# Schematic-Altium.net
KiCad netlist of a schematic drawn in Altium Designer
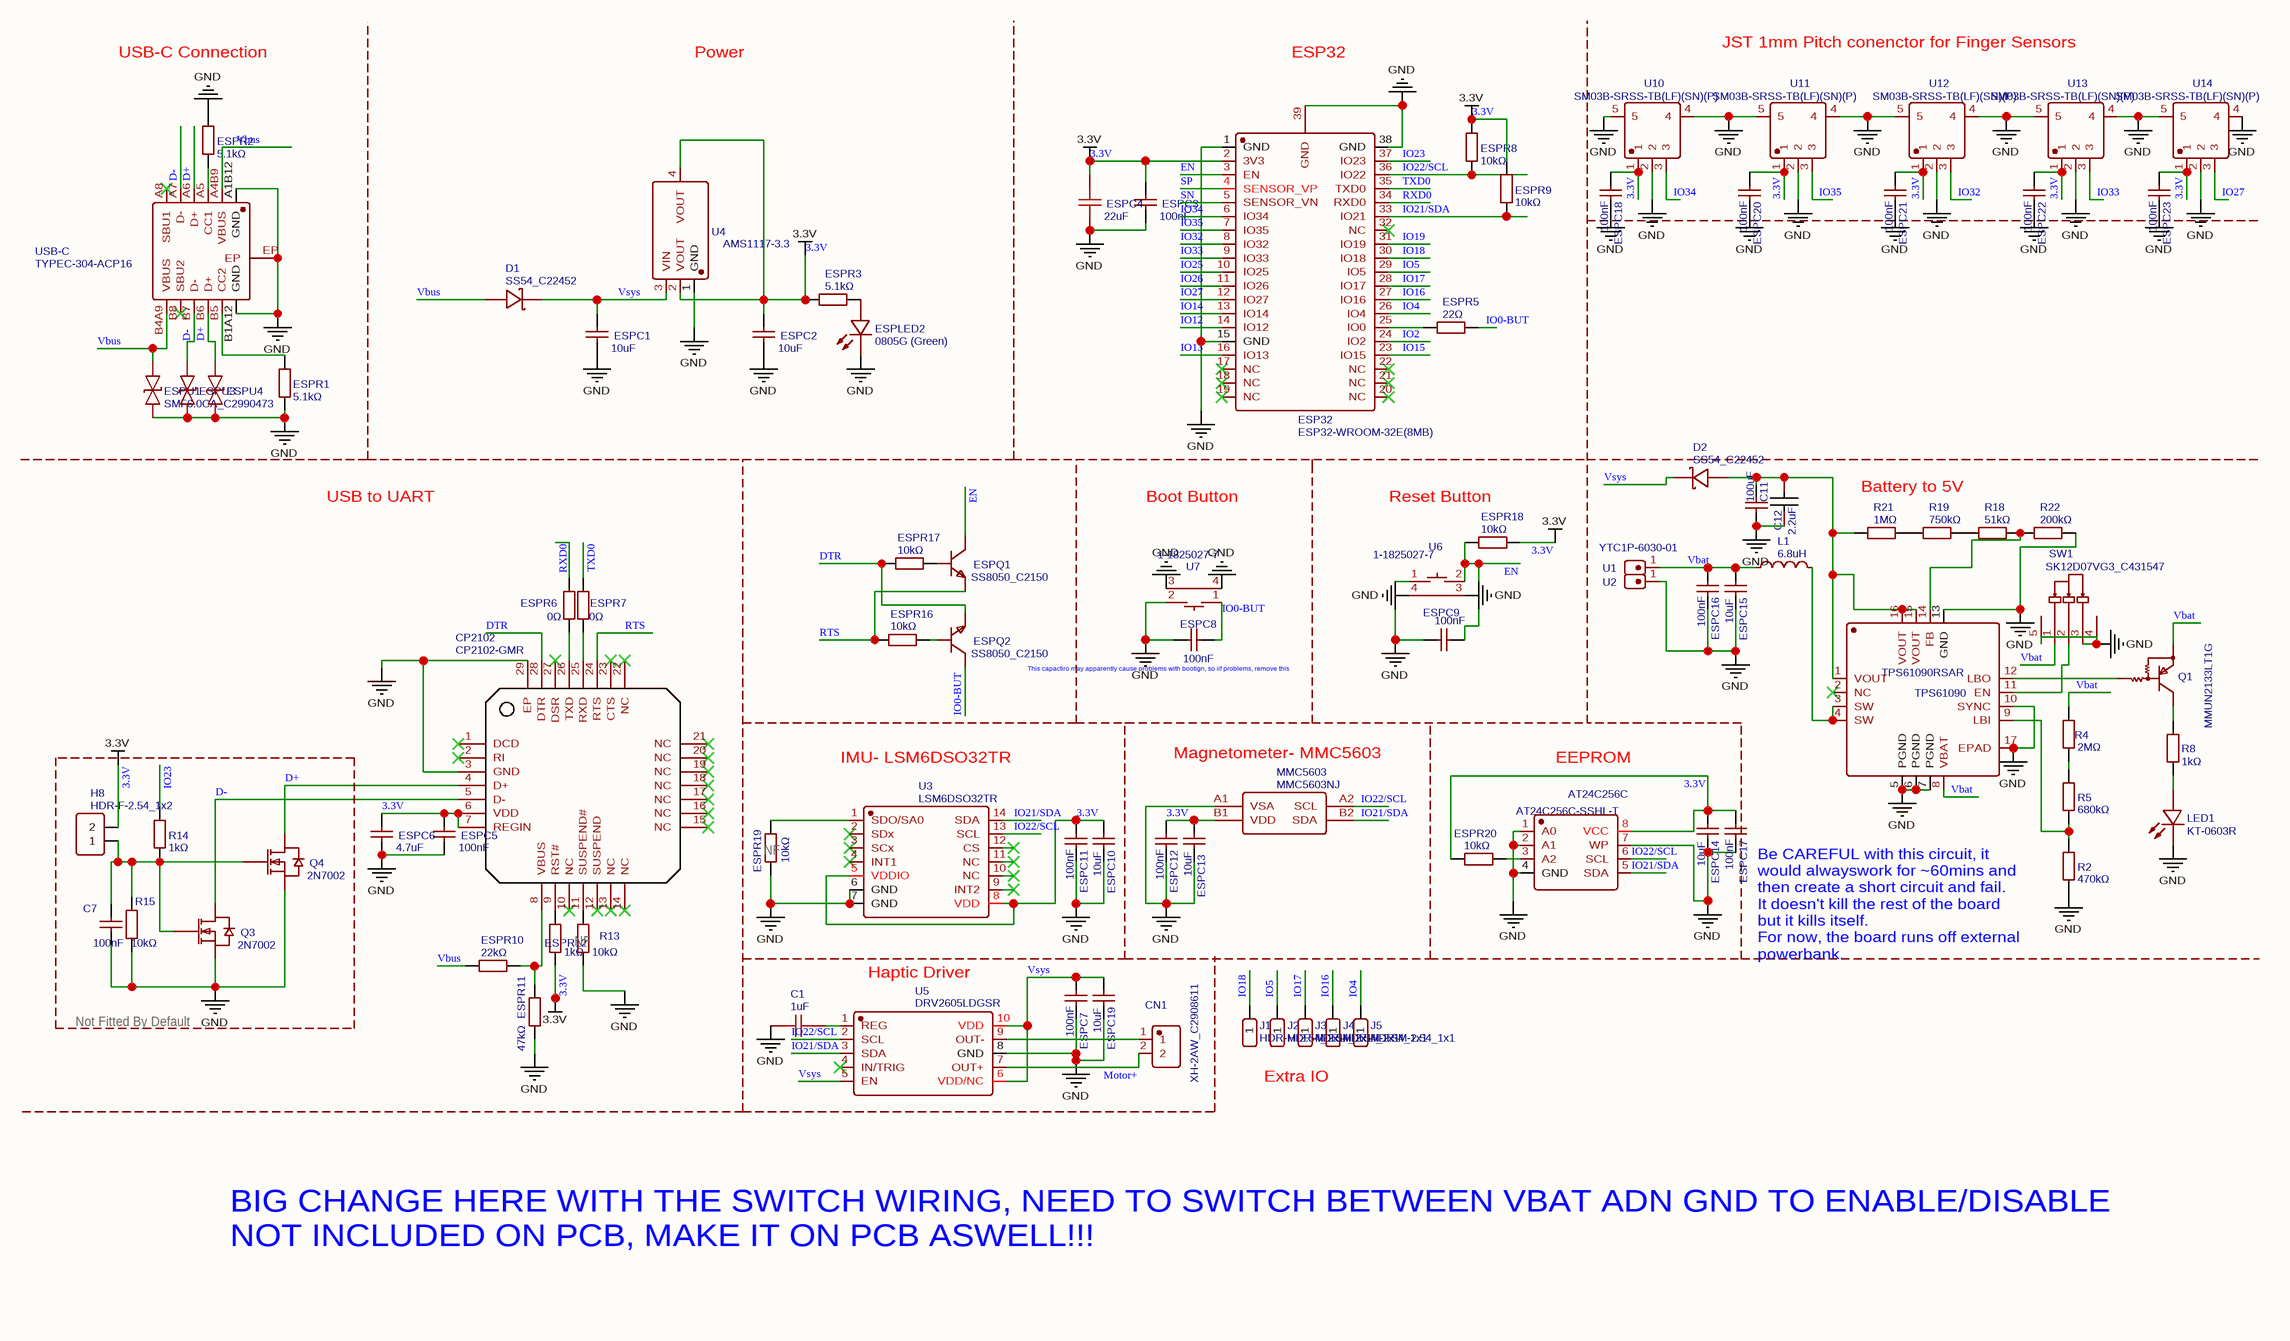
[diagram p0: Schematic-Altium.schdoc]

(export (version "E")
  (design (tool "Eeschema 10.0.6"))
  (components
    (comp (ref "AT24C256C")
      (value "AT24C256C-SSHL-T")
      (fields (field (name "MANUFACTURER") "MICROCHIP(美国微芯)"))
      (libsource (lib "altium-import") (part "root_0_AT24C256C-SSHL-T_"))
    )
    (comp (ref "C1")
      (value "1uF")
      (fields
        (field (name "MANUFACTURER") "SAMSUNG(三星)")
        (field (name "MANUFACTURER PART") "CL05A105KA5NQNC")
      )
      (libsource (lib "altium-import") (part "root_0_1uF_"))
    )
    (comp (ref "C7")
      (value "100nF")
      (fields
        (field (name "MANUFACTURER PART") "CL05B104KO5NNNC")
        (field (name "MANUFACTURER") "SAMSUNG(三星)")
      )
      (libsource (lib "altium-import") (part "root_1_100nF_"))
    )
    (comp (ref "C11")
      (value "100uF")
      (fields
        (field (name "MANUFACTURER PART") "CL31A107MQHNNNE")
        (field (name "MANUFACTURER") "SAMSUNG(三星)")
      )
      (libsource (lib "altium-import") (part "root_1_100uF_"))
    )
    (comp (ref "C12")
      (value "2.2uF")
      (fields
        (field (name "MANUFACTURER PART") "CL05A225MQ5NSNC")
        (field (name "MANUFACTURER") "SAMSUNG(三星)")
      )
      (libsource (lib "altium-import") (part "root_1_2.2uF_"))
    )
    (comp (ref "CN1")
      (value "XH-2AW_C2908611")
      (fields
        (field (name "MANUFACTURER") "HCTL(华灿天禄)")
        (field (name "MANUFACTURER PART") "XH-2AW")
        (field (name "CONTRIBUTOR") "LCSC")
      )
      (libsource (lib "altium-import") (part "root_0_XH-2AW_C2908611_"))
    )
    (comp (ref "CP2102")
      (value "CP2102-GMR")
      (fields (field (name "MANUFACTURER") "SILICON LABS(芯科)"))
      (libsource (lib "altium-import") (part "root_0_CP2102-GMR_"))
    )
    (comp (ref "D1")
      (value "SS54_C22452")
      (fields (field (name "MANUFACTURER PART") "SS54") (field (name "MANUFACTURER") "MDD"))
      (libsource (lib "altium-import") (part "root_2_SS54_C22452_"))
    )
    (comp (ref "D2")
      (value "SS54_C22452")
      (fields (field (name "MANUFACTURER PART") "SS54") (field (name "MANUFACTURER") "MDD"))
      (libsource (lib "altium-import") (part "root_0_SS54_C22452_"))
    )
    (comp (ref "ESP32")
      (value "ESP32-WROOM-32E(8MB)")
      (fields
        (field (name "MANUFACTURER") "ESPRESSIF(乐鑫)")
        (field (name "MANUFACTURER PART") "ESP32-WROOM-32E-N8")
        (field (name "CONTRIBUTOR") "LCSC")
      )
      (libsource (lib "altium-import") (part "root_0_ESP32-WROOM-32E(8MB)_"))
    )
    (comp (ref "ESPC1")
      (value "10uF")
      (fields
        (field (name "MANUFACTURER PART") "CL05A106MQ5NUNC")
        (field (name "MANUFACTURER") "SAMSUNG(三星)")
      )
      (libsource (lib "altium-import") (part "root_1_10uF_"))
    )
    (comp (ref "ESPC2")
      (value "10uF")
      (fields
        (field (name "MANUFACTURER PART") "CL05A106MQ5NUNC")
        (field (name "MANUFACTURER") "SAMSUNG(三星)")
      )
      (libsource (lib "altium-import") (part "root_1_10uF_"))
    )
    (comp (ref "ESPC3")
      (value "100nF")
      (fields
        (field (name "MANUFACTURER PART") "CL05B104KO5NNNC")
        (field (name "MANUFACTURER") "SAMSUNG(三星)")
      )
      (libsource (lib "altium-import") (part "root_1_100nF_"))
    )
    (comp (ref "ESPC4")
      (value "22uF")
      (fields
        (field (name "MANUFACTURER") "SAMSUNG(三星)")
        (field (name "MANUFACTURER PART") "CL10A226MQ8NRNC")
      )
      (libsource (lib "altium-import") (part "root_1_22uF_"))
    )
    (comp (ref "ESPC5")
      (value "100nF")
      (fields
        (field (name "MANUFACTURER PART") "CL05B104KO5NNNC")
        (field (name "MANUFACTURER") "SAMSUNG(三星)")
      )
      (libsource (lib "altium-import") (part "root_1_100nF_"))
    )
    (comp (ref "ESPC6")
      (value "4.7uF")
      (fields
        (field (name "MANUFACTURER PART") "CL05A475MP5NRNC")
        (field (name "MANUFACTURER") "SAMSUNG(三星)")
      )
      (libsource (lib "altium-import") (part "root_1_4.7uF_"))
    )
    (comp (ref "ESPC7")
      (value "100nF")
      (fields
        (field (name "MANUFACTURER PART") "CL05B104KO5NNNC")
        (field (name "MANUFACTURER") "SAMSUNG(三星)")
      )
      (libsource (lib "altium-import") (part "root_3_100nF_"))
    )
    (comp (ref "ESPC8")
      (value "100nF")
      (fields
        (field (name "MANUFACTURER PART") "CL05B104KO5NNNC")
        (field (name "MANUFACTURER") "SAMSUNG(三星)")
      )
      (libsource (lib "altium-import") (part "root_0_100nF_"))
    )
    (comp (ref "ESPC9")
      (value "100nF")
      (fields
        (field (name "MANUFACTURER PART") "CL05B104KO5NNNC")
        (field (name "MANUFACTURER") "SAMSUNG(三星)")
      )
      (libsource (lib "altium-import") (part "root_0_100nF_"))
    )
    (comp (ref "ESPC10")
      (value "10uF")
      (fields
        (field (name "MANUFACTURER PART") "CL05A106MQ5NUNC")
        (field (name "MANUFACTURER") "SAMSUNG(三星)")
      )
      (libsource (lib "altium-import") (part "root_1_10uF_"))
    )
    (comp (ref "ESPC11")
      (value "100nF")
      (fields
        (field (name "MANUFACTURER PART") "CL05B104KO5NNNC")
        (field (name "MANUFACTURER") "SAMSUNG(三星)")
      )
      (libsource (lib "altium-import") (part "root_3_100nF_"))
    )
    (comp (ref "ESPC12")
      (value "100nF")
      (fields
        (field (name "MANUFACTURER PART") "CL05B104KO5NNNC")
        (field (name "MANUFACTURER") "SAMSUNG(三星)")
      )
      (libsource (lib "altium-import") (part "root_3_100nF_"))
    )
    (comp (ref "ESPC13")
      (value "10uF")
      (fields
        (field (name "MANUFACTURER PART") "CL05A106MQ5NUNC")
        (field (name "MANUFACTURER") "SAMSUNG(三星)")
      )
      (libsource (lib "altium-import") (part "root_1_10uF_"))
    )
    (comp (ref "ESPC14")
      (value "10uF")
      (fields
        (field (name "MANUFACTURER PART") "CL05A106MQ5NUNC")
        (field (name "MANUFACTURER") "SAMSUNG(三星)")
      )
      (libsource (lib "altium-import") (part "root_1_10uF_"))
    )
    (comp (ref "ESPC15")
      (value "10uF")
      (fields
        (field (name "MANUFACTURER PART") "CL05A106MQ5NUNC")
        (field (name "MANUFACTURER") "SAMSUNG(三星)")
      )
      (libsource (lib "altium-import") (part "root_1_10uF_"))
    )
    (comp (ref "ESPC16")
      (value "100nF")
      (fields
        (field (name "MANUFACTURER PART") "CL05B104KO5NNNC")
        (field (name "MANUFACTURER") "SAMSUNG(三星)")
      )
      (libsource (lib "altium-import") (part "root_3_100nF_"))
    )
    (comp (ref "ESPC17")
      (value "100nF")
      (fields
        (field (name "MANUFACTURER PART") "CL05B104KO5NNNC")
        (field (name "MANUFACTURER") "SAMSUNG(三星)")
      )
      (libsource (lib "altium-import") (part "root_3_100nF_"))
    )
    (comp (ref "ESPC18")
      (value "100nF")
      (fields
        (field (name "MANUFACTURER PART") "CL05B104KO5NNNC")
        (field (name "MANUFACTURER") "SAMSUNG(三星)")
      )
      (libsource (lib "altium-import") (part "root_3_100nF_"))
    )
    (comp (ref "ESPC19")
      (value "10uF")
      (fields
        (field (name "MANUFACTURER PART") "CL05A106MQ5NUNC")
        (field (name "MANUFACTURER") "SAMSUNG(三星)")
      )
      (libsource (lib "altium-import") (part "root_1_10uF_"))
    )
    (comp (ref "ESPC20")
      (value "100nF")
      (fields
        (field (name "MANUFACTURER PART") "CL05B104KO5NNNC")
        (field (name "MANUFACTURER") "SAMSUNG(三星)")
      )
      (libsource (lib "altium-import") (part "root_3_100nF_"))
    )
    (comp (ref "ESPC21")
      (value "100nF")
      (fields
        (field (name "MANUFACTURER PART") "CL05B104KO5NNNC")
        (field (name "MANUFACTURER") "SAMSUNG(三星)")
      )
      (libsource (lib "altium-import") (part "root_3_100nF_"))
    )
    (comp (ref "ESPC22")
      (value "100nF")
      (fields
        (field (name "MANUFACTURER PART") "CL05B104KO5NNNC")
        (field (name "MANUFACTURER") "SAMSUNG(三星)")
      )
      (libsource (lib "altium-import") (part "root_3_100nF_"))
    )
    (comp (ref "ESPC23")
      (value "100nF")
      (fields
        (field (name "MANUFACTURER PART") "CL05B104KO5NNNC")
        (field (name "MANUFACTURER") "SAMSUNG(三星)")
      )
      (libsource (lib "altium-import") (part "root_3_100nF_"))
    )
    (comp (ref "ESPLED2")
      (value "0805G (Green)")
      (fields (field (name "MANUFACTURER") "KENTO") (field (name "MANUFACTURER PART") "KT-0805翠绿"))
      (libsource (lib "altium-import") (part "root_1_0805G (Green)_"))
    )
    (comp (ref "ESPQ1")
      (value "SS8050_C2150")
      (fields (field (name "MANUFACTURER") "CJ(江苏长电/长晶)") (field (name "MANUFACTURER PART") "SS8050"))
      (libsource (lib "altium-import") (part "root_0_SS8050_C2150_"))
    )
    (comp (ref "ESPQ2")
      (value "SS8050_C2150")
      (fields (field (name "MANUFACTURER") "CJ(江苏长电/长晶)") (field (name "MANUFACTURER PART") "SS8050"))
      (libsource (lib "") (part "root_0_SS8050_C2150__1"))
    )
    (comp (ref "ESPR1")
      (value "5.1kΩ")
      (fields
        (field (name "MANUFACTURER") "UNI-ROYAL(厚声)")
        (field (name "MANUFACTURER PART") "0402WGF5101TCE")
      )
      (libsource (lib "altium-import") (part "root_1_5.1kΩ_"))
    )
    (comp (ref "ESPR2")
      (value "5.1kΩ")
      (fields
        (field (name "MANUFACTURER") "UNI-ROYAL(厚声)")
        (field (name "MANUFACTURER PART") "0402WGF5101TCE")
      )
      (libsource (lib "altium-import") (part "root_1_5.1kΩ_"))
    )
    (comp (ref "ESPR3")
      (value "5.1kΩ")
      (fields
        (field (name "MANUFACTURER") "UNI-ROYAL(厚声)")
        (field (name "MANUFACTURER PART") "0402WGF5101TCE")
      )
      (libsource (lib "altium-import") (part "root_2_5.1kΩ_"))
    )
    (comp (ref "ESPR5")
      (value "22Ω")
      (fields
        (field (name "MANUFACTURER") "UNI-ROYAL(厚声)")
        (field (name "MANUFACTURER PART") "0402WGF220JTCE")
      )
      (libsource (lib "altium-import") (part "root_0_22Ω_"))
    )
    (comp (ref "ESPR6")
      (value "0Ω")
      (fields
        (field (name "MANUFACTURER") "UNI-ROYAL(厚声)")
        (field (name "MANUFACTURER PART") "0402WGF0000TCE")
      )
      (libsource (lib "altium-import") (part "root_1_0Ω_"))
    )
    (comp (ref "ESPR7")
      (value "0Ω")
      (fields
        (field (name "MANUFACTURER") "UNI-ROYAL(厚声)")
        (field (name "MANUFACTURER PART") "0402WGF0000TCE")
      )
      (libsource (lib "altium-import") (part "root_1_0Ω_"))
    )
    (comp (ref "ESPR8")
      (value "10kΩ")
      (fields
        (field (name "MANUFACTURER") "UNI-ROYAL(厚声)")
        (field (name "MANUFACTURER PART") "0402WGF1002TCE")
      )
      (libsource (lib "altium-import") (part "root_1_10kΩ_"))
    )
    (comp (ref "ESPR9")
      (value "10kΩ")
      (fields
        (field (name "MANUFACTURER") "UNI-ROYAL(厚声)")
        (field (name "MANUFACTURER PART") "0402WGF1002TCE")
      )
      (libsource (lib "altium-import") (part "root_1_10kΩ_"))
    )
    (comp (ref "ESPR10")
      (value "22kΩ")
      (fields
        (field (name "MANUFACTURER") "UNI-ROYAL(厚声)")
        (field (name "MANUFACTURER PART") "0402WGF2202TCE")
      )
      (libsource (lib "altium-import") (part "root_0_22kΩ_"))
    )
    (comp (ref "ESPR11")
      (value "47kΩ")
      (fields
        (field (name "MANUFACTURER") "UNI-ROYAL(厚声)")
        (field (name "MANUFACTURER PART") "0402WGF4702TCE")
      )
      (libsource (lib "altium-import") (part "root_1_47kΩ_"))
    )
    (comp (ref "ESPR12")
      (value "1kΩ")
      (fields
        (field (name "MANUFACTURER") "UNI-ROYAL(厚声)")
        (field (name "MANUFACTURER PART") "0402WGF1001TCE")
      )
      (libsource (lib "altium-import") (part "root_1_1kΩ_"))
    )
    (comp (ref "ESPR16")
      (value "10kΩ")
      (fields
        (field (name "MANUFACTURER") "UNI-ROYAL(厚声)")
        (field (name "MANUFACTURER PART") "0402WGF1002TCE")
      )
      (libsource (lib "altium-import") (part "root_2_10kΩ_"))
    )
    (comp (ref "ESPR17")
      (value "10kΩ")
      (fields
        (field (name "MANUFACTURER") "UNI-ROYAL(厚声)")
        (field (name "MANUFACTURER PART") "0402WGF1002TCE")
      )
      (libsource (lib "altium-import") (part "root_2_10kΩ_"))
    )
    (comp (ref "ESPR18")
      (value "10kΩ")
      (fields
        (field (name "MANUFACTURER") "UNI-ROYAL(厚声)")
        (field (name "MANUFACTURER PART") "0402WGF1002TCE")
      )
      (libsource (lib "altium-import") (part "root_2_10kΩ_"))
    )
    (comp (ref "ESPR19")
      (value "10kΩ")
      (fields
        (field (name "MANUFACTURER") "UNI-ROYAL(厚声)")
        (field (name "MANUFACTURER PART") "0402WGF1002TCE")
      )
      (libsource (lib "altium-import") (part "root_1_10kΩ_"))
    )
    (comp (ref "ESPR20")
      (value "10kΩ")
      (fields
        (field (name "MANUFACTURER") "UNI-ROYAL(厚声)")
        (field (name "MANUFACTURER PART") "0402WGF1002TCE")
      )
      (libsource (lib "altium-import") (part "root_2_10kΩ_"))
    )
    (comp (ref "ESPU1")
      (value "SMF6.0CA_C2990473")
      (fields
        (field (name "MANUFACTURER") "Liown(里阳半导体)")
        (field (name "MANUFACTURER PART") "SMF6.0CA")
        (field (name "CONTRIBUTOR") "lcsc")
      )
      (libsource (lib "altium-import") (part "root_1_SMF6.0CA_C2990473_"))
    )
    (comp (ref "ESPU3")
      (value "SMF6.0CA_C2990473")
      (fields
        (field (name "MANUFACTURER") "Liown(里阳半导体)")
        (field (name "MANUFACTURER PART") "SMF6.0CA")
        (field (name "CONTRIBUTOR") "lcsc")
      )
      (libsource (lib "altium-import") (part "root_1_SMF6.0CA_C2990473_"))
    )
    (comp (ref "ESPU4")
      (value "SMF6.0CA_C2990473")
      (fields
        (field (name "MANUFACTURER") "Liown(里阳半导体)")
        (field (name "MANUFACTURER PART") "SMF6.0CA")
        (field (name "CONTRIBUTOR") "lcsc")
      )
      (libsource (lib "altium-import") (part "root_1_SMF6.0CA_C2990473_"))
    )
    (comp (ref "H8")
      (value "HDR-F-2.54_1x2")
      (fields (field (name "CONTRIBUTOR") "LCEDA_Lib"))
      (libsource (lib "altium-import") (part "root_2_HDR-F-2.54_1x2_"))
    )
    (comp (ref "J1")
      (value "HDR-M-2.54_1x1")
      (fields (field (name "CONTRIBUTOR") "LCEDA_Lib"))
      (libsource (lib "altium-import") (part "root_3_HDR-M-2.54_1x1_"))
    )
    (comp (ref "J2")
      (value "HDR-M-2.54_1x1")
      (fields (field (name "CONTRIBUTOR") "LCEDA_Lib"))
      (libsource (lib "altium-import") (part "root_3_HDR-M-2.54_1x1_"))
    )
    (comp (ref "J3")
      (value "HDR-M-2.54_1x1")
      (fields (field (name "CONTRIBUTOR") "LCEDA_Lib"))
      (libsource (lib "altium-import") (part "root_3_HDR-M-2.54_1x1_"))
    )
    (comp (ref "J4")
      (value "HDR-M-2.54_1x1")
      (fields (field (name "CONTRIBUTOR") "LCEDA_Lib"))
      (libsource (lib "altium-import") (part "root_3_HDR-M-2.54_1x1_"))
    )
    (comp (ref "J5")
      (value "HDR-M-2.54_1x1")
      (fields (field (name "CONTRIBUTOR") "LCEDA_Lib"))
      (libsource (lib "altium-import") (part "root_3_HDR-M-2.54_1x1_"))
    )
    (comp (ref "L1")
      (value "6.8uH")
      (fields
        (field (name "MANUFACTURER") "SXN(顺翔诺)")
        (field (name "MANUFACTURER PART") "SMMS0420-6R8M")
        (field (name "CONTRIBUTOR") "LCSC")
      )
      (libsource (lib "altium-import") (part "root_0_6.8uH_"))
    )
    (comp (ref "LED1")
      (value "KT-0603R")
      (fields (field (name "MANUFACTURER") "KENTO"))
      (libsource (lib "altium-import") (part "root_1_KT-0603R_"))
    )
    (comp (ref "MMC5603")
      (value "MMC5603NJ")
      (fields (field (name "MANUFACTURER") "MEMSIC(美新)") (field (name "CONTRIBUTOR") "LCSC"))
      (libsource (lib "altium-import") (part "root_0_MMC5603NJ_"))
    )
    (comp (ref "Q1")
      (value "MMUN2133LT1G")
      (fields (field (name "MANUFACTURER") "onsemi(安森美)"))
      (libsource (lib "altium-import") (part "root_0_MMUN2133LT1G_"))
    )
    (comp (ref "Q3")
      (value "2N7002")
      (fields (field (name "MANUFACTURER") "CJ(江苏长电/长晶)"))
      (libsource (lib "altium-import") (part "root_0_2N7002_"))
    )
    (comp (ref "Q4")
      (value "2N7002")
      (fields (field (name "MANUFACTURER") "CJ(江苏长电/长晶)"))
      (libsource (lib "altium-import") (part "root_0_2N7002_"))
    )
    (comp (ref "R2")
      (value "470kΩ")
      (fields
        (field (name "MANUFACTURER") "UNI-ROYAL(厚声)")
        (field (name "MANUFACTURER PART") "0402WGF4703TCE")
      )
      (libsource (lib "altium-import") (part "root_1_470kΩ_"))
    )
    (comp (ref "R4")
      (value "2MΩ")
      (fields
        (field (name "MANUFACTURER") "UNI-ROYAL(厚声)")
        (field (name "MANUFACTURER PART") "0603WAF2004T5E")
      )
      (libsource (lib "altium-import") (part "root_1_2MΩ_"))
    )
    (comp (ref "R5")
      (value "680kΩ")
      (fields
        (field (name "MANUFACTURER") "UNI-ROYAL(厚声)")
        (field (name "MANUFACTURER PART") "0603WAF6803T5E")
      )
      (libsource (lib "altium-import") (part "root_1_680kΩ_"))
    )
    (comp (ref "R8")
      (value "1kΩ")
      (fields
        (field (name "MANUFACTURER") "UNI-ROYAL(厚声)")
        (field (name "MANUFACTURER PART") "0402WGF1001TCE")
      )
      (libsource (lib "altium-import") (part "root_1_1kΩ_"))
    )
    (comp (ref "R13")
      (value "10kΩ")
      (fields
        (field (name "MANUFACTURER") "UNI-ROYAL(厚声)")
        (field (name "MANUFACTURER PART") "0402WGF1002TCE")
      )
      (libsource (lib "altium-import") (part "root_1_10kΩ_"))
    )
    (comp (ref "R14")
      (value "1kΩ")
      (fields
        (field (name "MANUFACTURER") "UNI-ROYAL(厚声)")
        (field (name "MANUFACTURER PART") "0402WGF1001TCE")
      )
      (libsource (lib "altium-import") (part "root_1_1kΩ_"))
    )
    (comp (ref "R15")
      (value "10kΩ")
      (fields
        (field (name "MANUFACTURER") "UNI-ROYAL(厚声)")
        (field (name "MANUFACTURER PART") "0402WGF1002TCE")
      )
      (libsource (lib "altium-import") (part "root_1_10kΩ_"))
    )
    (comp (ref "R18")
      (value "51kΩ")
      (fields
        (field (name "MANUFACTURER") "UNI-ROYAL(厚声)")
        (field (name "MANUFACTURER PART") "0402WGF5102TCE")
      )
      (libsource (lib "altium-import") (part "root_0_51kΩ_"))
    )
    (comp (ref "R19")
      (value "750kΩ")
      (fields
        (field (name "MANUFACTURER") "UNI-ROYAL(厚声)")
        (field (name "MANUFACTURER PART") "0603WAF7503T5E")
      )
      (libsource (lib "altium-import") (part "root_0_750kΩ_"))
    )
    (comp (ref "R21")
      (value "1MΩ")
      (fields
        (field (name "MANUFACTURER") "UNI-ROYAL(厚声)")
        (field (name "MANUFACTURER PART") "0402WGF1004TCE")
      )
      (libsource (lib "altium-import") (part "root_0_1MΩ_"))
    )
    (comp (ref "R22")
      (value "200kΩ")
      (fields
        (field (name "MANUFACTURER") "UNI-ROYAL(厚声)")
        (field (name "MANUFACTURER PART") "0402WGF2003TCE")
      )
      (libsource (lib "altium-import") (part "root_0_200kΩ_"))
    )
    (comp (ref "SW1")
      (value "SK12D07VG3_C431547")
      (fields
        (field (name "MANUFACTURER") "SHOU HAN")
        (field (name "MANUFACTURER PART") "SK12D07VG3")
        (field (name "CONTRIBUTOR") "LCSC")
      )
      (libsource (lib "altium-import") (part "root_0_SK12D07VG3_C431547_"))
    )
    (comp (ref "TPS61090")
      (value "TPS61090RSAR")
      (fields (field (name "MANUFACTURER") "TI(德州仪器)") (field (name "CONTRIBUTOR") "LCSC"))
      (libsource (lib "altium-import") (part "root_0_TPS61090RSAR_"))
    )
    (comp (ref "U1")
      (value "YTC1P-6030-01")
      (fields (field (name "MANUFACTURER") "YIYUAN(怡远)") (field (name "CONTRIBUTOR") "lcsc"))
      (libsource (lib "altium-import") (part "root_2_YTC1P-6030-01_"))
    )
    (comp (ref "U2")
      (value "YTC1P-6030-01")
      (fields (field (name "MANUFACTURER") "YIYUAN(怡远)") (field (name "CONTRIBUTOR") "lcsc"))
      (libsource (lib "altium-import") (part "root_2_YTC1P-6030-01_"))
    )
    (comp (ref "U3")
      (value "LSM6DSO32TR")
      (fields (field (name "MANUFACTURER") "ST(意法半导体)") (field (name "CONTRIBUTOR") "LCSC"))
      (libsource (lib "altium-import") (part "root_0_LSM6DSO32TR_"))
    )
    (comp (ref "U4")
      (value "AMS1117-3.3")
      (fields (field (name "MANUFACTURER") "AMS"))
      (libsource (lib "altium-import") (part "root_1_AMS1117-3.3_"))
    )
    (comp (ref "U5")
      (value "DRV2605LDGSR")
      (fields (field (name "MANUFACTURER") "TI(德州仪器)") (field (name "CONTRIBUTOR") "LCSC"))
      (libsource (lib "altium-import") (part "root_0_DRV2605LDGSR_"))
    )
    (comp (ref "U6")
      (value "1-1825027-7")
      (fields (field (name "MANUFACTURER") "TE Connectivity(美国泰科)") (field (name "CONTRIBUTOR") "lcsc"))
      (libsource (lib "altium-import") (part "root_0_1-1825027-7_"))
    )
    (comp (ref "U7")
      (value "1-1825027-7")
      (fields (field (name "MANUFACTURER") "TE Connectivity(美国泰科)") (field (name "CONTRIBUTOR") "lcsc"))
      (libsource (lib "altium-import") (part "root_2_1-1825027-7_"))
    )
    (comp (ref "U10")
      (value "SM03B-SRSS-TB(LF)(SN)(P)")
      (fields
        (field (name "MANUFACTURER") "JST")
        (field (name "MANUFACTURER PART") "SM03B-SRSS-TB(LF)(SN)")
        (field (name "CONTRIBUTOR") "LCSC")
      )
      (libsource (lib "altium-import") (part "root_1_SM03B-SRSS-TB(LF)(SN)(P)_"))
    )
    (comp (ref "U11")
      (value "SM03B-SRSS-TB(LF)(SN)(P)")
      (fields
        (field (name "MANUFACTURER") "JST")
        (field (name "MANUFACTURER PART") "SM03B-SRSS-TB(LF)(SN)")
        (field (name "CONTRIBUTOR") "LCSC")
      )
      (libsource (lib "altium-import") (part "root_1_SM03B-SRSS-TB(LF)(SN)(P)_"))
    )
    (comp (ref "U12")
      (value "SM03B-SRSS-TB(LF)(SN)(P)")
      (fields
        (field (name "MANUFACTURER") "JST")
        (field (name "MANUFACTURER PART") "SM03B-SRSS-TB(LF)(SN)")
        (field (name "CONTRIBUTOR") "LCSC")
      )
      (libsource (lib "altium-import") (part "root_1_SM03B-SRSS-TB(LF)(SN)(P)_"))
    )
    (comp (ref "U13")
      (value "SM03B-SRSS-TB(LF)(SN)(P)")
      (fields
        (field (name "MANUFACTURER") "JST")
        (field (name "MANUFACTURER PART") "SM03B-SRSS-TB(LF)(SN)")
        (field (name "CONTRIBUTOR") "LCSC")
      )
      (libsource (lib "altium-import") (part "root_1_SM03B-SRSS-TB(LF)(SN)(P)_"))
    )
    (comp (ref "U14")
      (value "SM03B-SRSS-TB(LF)(SN)(P)")
      (fields
        (field (name "MANUFACTURER") "JST")
        (field (name "MANUFACTURER PART") "SM03B-SRSS-TB(LF)(SN)")
        (field (name "CONTRIBUTOR") "LCSC")
      )
      (libsource (lib "altium-import") (part "root_1_SM03B-SRSS-TB(LF)(SN)(P)_"))
    )
    (comp (ref "USB-C")
      (value "TYPEC-304-ACP16")
      (fields (field (name "MANUFACTURER") "XUNPU(讯普)") (field (name "CONTRIBUTOR") "LCSC"))
      (libsource (lib "altium-import") (part "root_3_TYPEC-304-ACP16_"))
    )
  )
  (nets
    (net (code "1") (name "/D+") (class "Default")
      (node (ref "CP2102") (pin "4") (pinfunction "D+_4") (pintype "passive"))
      (node (ref "ESPU4") (pin "2") (pinfunction "2_2") (pintype "passive"))
      (node (ref "Q4") (pin "3") (pinfunction "D_3") (pintype "passive"))
      (node (ref "USB-C") (pin "A6") (pinfunction "D+_A6") (pintype "passive"))
      (node (ref "USB-C") (pin "B6") (pinfunction "D+_B6") (pintype "passive"))
    )
    (net (code "2") (name "/D-") (class "Default")
      (node (ref "CP2102") (pin "5") (pinfunction "D-_5") (pintype "passive"))
      (node (ref "ESPU3") (pin "2") (pinfunction "2_2") (pintype "passive"))
      (node (ref "Q3") (pin "3") (pinfunction "D_3") (pintype "passive"))
      (node (ref "USB-C") (pin "A7") (pinfunction "D-_A7") (pintype "passive"))
      (node (ref "USB-C") (pin "B7") (pinfunction "D-_B7") (pintype "passive"))
    )
    (net (code "3") (name "/DTR") (class "Default")
      (node (ref "CP2102") (pin "28") (pinfunction "DTR_28") (pintype "passive"))
      (node (ref "ESPQ2") (pin "2") (pinfunction "E_2") (pintype "passive"))
      (node (ref "ESPR17") (pin "2") (pinfunction "2_2") (pintype "passive"))
    )
    (net (code "4") (name "/EN") (class "Default")
      (node (ref "ESP32") (pin "3") (pinfunction "EN_3") (pintype "passive"))
      (node (ref "ESPC9") (pin "2") (pinfunction "2_2") (pintype "passive"))
      (node (ref "ESPQ1") (pin "3") (pinfunction "C_3") (pintype "passive"))
      (node (ref "ESPR18") (pin "2") (pinfunction "2_2") (pintype "passive"))
      (node (ref "U6") (pin "2") (pinfunction "2_2") (pintype "passive"))
    )
    (net (code "5") (name "/IO0-BUT") (class "Default")
      (node (ref "ESPC8") (pin "2") (pinfunction "2_2") (pintype "passive"))
      (node (ref "ESPQ2") (pin "3") (pinfunction "C_3") (pintype "passive"))
      (node (ref "ESPR5") (pin "2") (pinfunction "2_2") (pintype "passive"))
      (node (ref "U7") (pin "1") (pinfunction "1_1") (pintype "passive"))
    )
    (net (code "6") (name "/IO2") (class "Default")
      (node (ref "ESP32") (pin "24") (pinfunction "IO2_24") (pintype "passive"))
    )
    (net (code "7") (name "/IO4") (class "Default")
      (node (ref "ESP32") (pin "26") (pinfunction "IO4_26") (pintype "passive"))
      (node (ref "J5") (pin "1") (pinfunction "1_1") (pintype "passive"))
    )
    (net (code "8") (name "/IO5") (class "Default")
      (node (ref "ESP32") (pin "29") (pinfunction "IO5_29") (pintype "passive"))
      (node (ref "J2") (pin "1") (pinfunction "1_1") (pintype "passive"))
    )
    (net (code "9") (name "/IO12") (class "Default")
      (node (ref "ESP32") (pin "14") (pinfunction "IO12_14") (pintype "passive"))
    )
    (net (code "10") (name "/IO13") (class "Default")
      (node (ref "ESP32") (pin "16") (pinfunction "IO13_16") (pintype "passive"))
    )
    (net (code "11") (name "/IO14") (class "Default")
      (node (ref "ESP32") (pin "13") (pinfunction "IO14_13") (pintype "passive"))
    )
    (net (code "12") (name "/IO15") (class "Default")
      (node (ref "ESP32") (pin "23") (pinfunction "IO15_23") (pintype "passive"))
    )
    (net (code "13") (name "/IO16") (class "Default")
      (node (ref "ESP32") (pin "27") (pinfunction "IO16_27") (pintype "passive"))
      (node (ref "J4") (pin "1") (pinfunction "1_1") (pintype "passive"))
    )
    (net (code "14") (name "/IO17") (class "Default")
      (node (ref "ESP32") (pin "28") (pinfunction "IO17_28") (pintype "passive"))
      (node (ref "J3") (pin "1") (pinfunction "1_1") (pintype "passive"))
    )
    (net (code "15") (name "/IO18") (class "Default")
      (node (ref "ESP32") (pin "30") (pinfunction "IO18_30") (pintype "passive"))
      (node (ref "J1") (pin "1") (pinfunction "1_1") (pintype "passive"))
    )
    (net (code "16") (name "/IO19") (class "Default")
      (node (ref "ESP32") (pin "31") (pinfunction "IO19_31") (pintype "passive"))
    )
    (net (code "17") (name "/IO21{slash}SDA") (class "Default")
      (node (ref "AT24C256C") (pin "5") (pinfunction "SDA_5") (pintype "passive"))
      (node (ref "ESP32") (pin "33") (pinfunction "IO21_33") (pintype "passive"))
      (node (ref "ESPR9") (pin "1") (pinfunction "1_1") (pintype "passive"))
      (node (ref "MMC5603") (pin "B2") (pinfunction "SDA_B2") (pintype "passive"))
      (node (ref "U3") (pin "14") (pinfunction "SDA_14") (pintype "passive"))
      (node (ref "U5") (pin "3") (pinfunction "SDA_3") (pintype "passive"))
    )
    (net (code "18") (name "/IO22{slash}SCL") (class "Default")
      (node (ref "AT24C256C") (pin "6") (pinfunction "SCL_6") (pintype "passive"))
      (node (ref "ESP32") (pin "36") (pinfunction "IO22_36") (pintype "passive"))
      (node (ref "ESPR8") (pin "1") (pinfunction "1_1") (pintype "passive"))
      (node (ref "MMC5603") (pin "A2") (pinfunction "SCL_A2") (pintype "passive"))
      (node (ref "U3") (pin "13") (pinfunction "SCL_13") (pintype "passive"))
      (node (ref "U5") (pin "2") (pinfunction "SCL_2") (pintype "passive"))
    )
    (net (code "19") (name "/IO23") (class "Default")
      (node (ref "ESP32") (pin "37") (pinfunction "IO23_37") (pintype "passive"))
      (node (ref "R14") (pin "2") (pinfunction "2_2") (pintype "passive"))
    )
    (net (code "20") (name "/IO25") (class "Default")
      (node (ref "ESP32") (pin "10") (pinfunction "IO25_10") (pintype "passive"))
    )
    (net (code "21") (name "/IO26") (class "Default")
      (node (ref "ESP32") (pin "11") (pinfunction "IO26_11") (pintype "passive"))
    )
    (net (code "22") (name "/IO27") (class "Default")
      (node (ref "ESP32") (pin "12") (pinfunction "IO27_12") (pintype "passive"))
      (node (ref "U14") (pin "3") (pinfunction "3_3") (pintype "passive"))
    )
    (net (code "23") (name "/IO32") (class "Default")
      (node (ref "ESP32") (pin "8") (pinfunction "IO32_8") (pintype "passive"))
      (node (ref "U12") (pin "3") (pinfunction "3_3") (pintype "passive"))
    )
    (net (code "24") (name "/IO33") (class "Default")
      (node (ref "ESP32") (pin "9") (pinfunction "IO33_9") (pintype "passive"))
      (node (ref "U13") (pin "3") (pinfunction "3_3") (pintype "passive"))
    )
    (net (code "25") (name "/IO34") (class "Default")
      (node (ref "ESP32") (pin "6") (pinfunction "IO34_6") (pintype "passive"))
      (node (ref "U10") (pin "3") (pinfunction "3_3") (pintype "passive"))
    )
    (net (code "26") (name "/IO35") (class "Default")
      (node (ref "ESP32") (pin "7") (pinfunction "IO35_7") (pintype "passive"))
      (node (ref "U11") (pin "3") (pinfunction "3_3") (pintype "passive"))
    )
    (net (code "27") (name "/Motor+") (class "Default")
      (node (ref "CN1") (pin "2") (pinfunction "2_2") (pintype "passive"))
      (node (ref "U5") (pin "7") (pinfunction "OUT+_7") (pintype "passive"))
    )
    (net (code "28") (name "/RTS") (class "Default")
      (node (ref "CP2102") (pin "24") (pinfunction "RTS_24") (pintype "passive"))
      (node (ref "ESPQ1") (pin "2") (pinfunction "E_2") (pintype "passive"))
      (node (ref "ESPR16") (pin "2") (pinfunction "2_2") (pintype "passive"))
    )
    (net (code "29") (name "/RXD0") (class "Default")
      (node (ref "ESP32") (pin "34") (pinfunction "RXD0_34") (pintype "passive"))
      (node (ref "ESPR6") (pin "2") (pinfunction "2_2") (pintype "passive"))
    )
    (net (code "30") (name "/SN") (class "Default")
      (node (ref "ESP32") (pin "5") (pinfunction "SENSOR_VN_5") (pintype "passive"))
    )
    (net (code "31") (name "/SP") (class "Default")
      (node (ref "ESP32") (pin "4") (pinfunction "SENSOR_VP_4") (pintype "passive"))
    )
    (net (code "32") (name "/TXD0") (class "Default")
      (node (ref "ESP32") (pin "35") (pinfunction "TXD0_35") (pintype "passive"))
      (node (ref "ESPR7") (pin "2") (pinfunction "2_2") (pintype "passive"))
    )
    (net (code "33") (name "/Vbat") (class "Default")
      (node (ref "ESPC15") (pin "2") (pinfunction "2_2") (pintype "passive"))
      (node (ref "ESPC16") (pin "1") (pinfunction "1_1") (pintype "passive"))
      (node (ref "L1") (pin "1") (pinfunction "1_1") (pintype "passive"))
      (node (ref "Q1") (pin "2") (pinfunction "E_2") (pintype "passive"))
      (node (ref "R4") (pin "2") (pinfunction "2_2") (pintype "passive"))
      (node (ref "SW1") (pin "1") (pinfunction "1_1") (pintype "passive"))
      (node (ref "TPS61090") (pin "8") (pinfunction "VBAT_8") (pintype "passive"))
      (node (ref "U1") (pin "1") (pinfunction "1_1") (pintype "passive"))
    )
    (net (code "34") (name "/Vbus") (class "Default")
      (node (ref "D1") (pin "1") (pinfunction "A_1") (pintype "passive"))
      (node (ref "ESPR10") (pin "1") (pinfunction "1_1") (pintype "passive"))
      (node (ref "ESPU1") (pin "2") (pinfunction "2_2") (pintype "passive"))
      (node (ref "USB-C") (pin "A4B9") (pinfunction "VBUS_A4B9") (pintype "passive"))
      (node (ref "USB-C") (pin "B4A9") (pinfunction "VBUS_B4A9") (pintype "passive"))
    )
    (net (code "35") (name "/Vsys") (class "Default")
      (node (ref "D1") (pin "2") (pinfunction "K_2") (pintype "passive"))
      (node (ref "D2") (pin "2") (pinfunction "K_2") (pintype "passive"))
      (node (ref "ESPC1") (pin "2") (pinfunction "2_2") (pintype "passive"))
      (node (ref "ESPC19") (pin "2") (pinfunction "2_2") (pintype "passive"))
      (node (ref "ESPC7") (pin "1") (pinfunction "1_1") (pintype "passive"))
      (node (ref "U4") (pin "3") (pinfunction "VIN_3") (pintype "passive"))
      (node (ref "U5") (pin "10") (pinfunction "VDD_10") (pintype "passive"))
      (node (ref "U5") (pin "5") (pinfunction "EN_5") (pintype "passive"))
      (node (ref "U5") (pin "6") (pinfunction "VDD/NC_6") (pintype "passive"))
    )
    (net (code "36") (name "3.3V") (class "Default")
      (node (ref "AT24C256C") (pin "8") (pinfunction "VCC_8") (pintype "passive"))
      (node (ref "CP2102") (pin "6") (pinfunction "VDD_6") (pintype "passive"))
      (node (ref "CP2102") (pin "7") (pinfunction "REGIN_7") (pintype "passive"))
      (node (ref "ESP32") (pin "2") (pinfunction "3V3_2") (pintype "passive"))
      (node (ref "ESPC10") (pin "2") (pinfunction "2_2") (pintype "passive"))
      (node (ref "ESPC11") (pin "1") (pinfunction "1_1") (pintype "passive"))
      (node (ref "ESPC12") (pin "1") (pinfunction "1_1") (pintype "passive"))
      (node (ref "ESPC13") (pin "2") (pinfunction "2_2") (pintype "passive"))
      (node (ref "ESPC14") (pin "2") (pinfunction "2_2") (pintype "passive"))
      (node (ref "ESPC17") (pin "1") (pinfunction "1_1") (pintype "passive"))
      (node (ref "ESPC18") (pin "1") (pinfunction "1_1") (pintype "passive"))
      (node (ref "ESPC2") (pin "2") (pinfunction "2_2") (pintype "passive"))
      (node (ref "ESPC20") (pin "1") (pinfunction "1_1") (pintype "passive"))
      (node (ref "ESPC21") (pin "1") (pinfunction "1_1") (pintype "passive"))
      (node (ref "ESPC22") (pin "1") (pinfunction "1_1") (pintype "passive"))
      (node (ref "ESPC23") (pin "1") (pinfunction "1_1") (pintype "passive"))
      (node (ref "ESPC3") (pin "2") (pinfunction "2_2") (pintype "passive"))
      (node (ref "ESPC4") (pin "2") (pinfunction "2_2") (pintype "passive"))
      (node (ref "ESPC5") (pin "2") (pinfunction "2_2") (pintype "passive"))
      (node (ref "ESPC6") (pin "2") (pinfunction "2_2") (pintype "passive"))
      (node (ref "ESPR12") (pin "1") (pinfunction "1_1") (pintype "passive"))
      (node (ref "ESPR18") (pin "1") (pinfunction "1_1") (pintype "passive"))
      (node (ref "ESPR20") (pin "2") (pinfunction "2_2") (pintype "passive"))
      (node (ref "ESPR3") (pin "2") (pinfunction "2_2") (pintype "passive"))
      (node (ref "ESPR8") (pin "2") (pinfunction "2_2") (pintype "passive"))
      (node (ref "ESPR9") (pin "2") (pinfunction "2_2") (pintype "passive"))
      (node (ref "H8") (pin "2") (pinfunction "2_2") (pintype "passive"))
      (node (ref "MMC5603") (pin "B1") (pinfunction "VDD_B1") (pintype "passive"))
      (node (ref "U10") (pin "1") (pinfunction "1_1") (pintype "passive"))
      (node (ref "U11") (pin "1") (pinfunction "1_1") (pintype "passive"))
      (node (ref "U12") (pin "1") (pinfunction "1_1") (pintype "passive"))
      (node (ref "U13") (pin "1") (pinfunction "1_1") (pintype "passive"))
      (node (ref "U14") (pin "1") (pinfunction "1_1") (pintype "passive"))
      (node (ref "U3") (pin "5") (pinfunction "VDDIO_5") (pintype "passive"))
      (node (ref "U3") (pin "8") (pinfunction "VDD_8") (pintype "passive"))
      (node (ref "U4") (pin "2") (pinfunction "VOUT_2") (pintype "passive"))
      (node (ref "U4") (pin "4") (pinfunction "VOUT_4") (pintype "passive"))
    )
    (net (code "37") (name "GND") (class "Default")
      (node (ref "AT24C256C") (pin "1") (pinfunction "A0_1") (pintype "passive"))
      (node (ref "AT24C256C") (pin "2") (pinfunction "A1_2") (pintype "passive"))
      (node (ref "AT24C256C") (pin "4") (pinfunction "GND_4") (pintype "passive"))
      (node (ref "AT24C256C") (pin "7") (pinfunction "WP_7") (pintype "passive"))
      (node (ref "C1") (pin "1") (pinfunction "1_1") (pintype "passive"))
      (node (ref "C11") (pin "1") (pinfunction "1_1") (pintype "passive"))
      (node (ref "C12") (pin "1") (pinfunction "1_1") (pintype "passive"))
      (node (ref "C7") (pin "1") (pinfunction "1_1") (pintype "passive"))
      (node (ref "CP2102") (pin "29") (pinfunction "EP_29") (pintype "passive"))
      (node (ref "CP2102") (pin "3") (pinfunction "GND_3") (pintype "passive"))
      (node (ref "ESP32") (pin "1") (pinfunction "GND_1") (pintype "passive"))
      (node (ref "ESP32") (pin "15") (pinfunction "GND_15") (pintype "passive"))
      (node (ref "ESP32") (pin "38") (pinfunction "GND_38") (pintype "passive"))
      (node (ref "ESP32") (pin "39") (pinfunction "GND_39") (pintype "passive"))
      (node (ref "ESPC1") (pin "1") (pinfunction "1_1") (pintype "passive"))
      (node (ref "ESPC10") (pin "1") (pinfunction "1_1") (pintype "passive"))
      (node (ref "ESPC11") (pin "2") (pinfunction "2_2") (pintype "passive"))
      (node (ref "ESPC12") (pin "2") (pinfunction "2_2") (pintype "passive"))
      (node (ref "ESPC13") (pin "1") (pinfunction "1_1") (pintype "passive"))
      (node (ref "ESPC14") (pin "1") (pinfunction "1_1") (pintype "passive"))
      (node (ref "ESPC15") (pin "1") (pinfunction "1_1") (pintype "passive"))
      (node (ref "ESPC16") (pin "2") (pinfunction "2_2") (pintype "passive"))
      (node (ref "ESPC17") (pin "2") (pinfunction "2_2") (pintype "passive"))
      (node (ref "ESPC18") (pin "2") (pinfunction "2_2") (pintype "passive"))
      (node (ref "ESPC19") (pin "1") (pinfunction "1_1") (pintype "passive"))
      (node (ref "ESPC2") (pin "1") (pinfunction "1_1") (pintype "passive"))
      (node (ref "ESPC20") (pin "2") (pinfunction "2_2") (pintype "passive"))
      (node (ref "ESPC21") (pin "2") (pinfunction "2_2") (pintype "passive"))
      (node (ref "ESPC22") (pin "2") (pinfunction "2_2") (pintype "passive"))
      (node (ref "ESPC23") (pin "2") (pinfunction "2_2") (pintype "passive"))
      (node (ref "ESPC3") (pin "1") (pinfunction "1_1") (pintype "passive"))
      (node (ref "ESPC4") (pin "1") (pinfunction "1_1") (pintype "passive"))
      (node (ref "ESPC5") (pin "1") (pinfunction "1_1") (pintype "passive"))
      (node (ref "ESPC6") (pin "1") (pinfunction "1_1") (pintype "passive"))
      (node (ref "ESPC7") (pin "2") (pinfunction "2_2") (pintype "passive"))
      (node (ref "ESPC8") (pin "1") (pinfunction "1_1") (pintype "passive"))
      (node (ref "ESPC9") (pin "1") (pinfunction "1_1") (pintype "passive"))
      (node (ref "ESPLED2") (pin "2") (pinfunction "K_2") (pintype "passive"))
      (node (ref "ESPR1") (pin "1") (pinfunction "1_1") (pintype "passive"))
      (node (ref "ESPR11") (pin "1") (pinfunction "1_1") (pintype "passive"))
      (node (ref "ESPR19") (pin "1") (pinfunction "1_1") (pintype "passive"))
      (node (ref "ESPR2") (pin "2") (pinfunction "2_2") (pintype "passive"))
      (node (ref "ESPU1") (pin "1") (pinfunction "1_1") (pintype "passive"))
      (node (ref "ESPU3") (pin "1") (pinfunction "1_1") (pintype "passive"))
      (node (ref "ESPU4") (pin "1") (pinfunction "1_1") (pintype "passive"))
      (node (ref "LED1") (pin "1") (pinfunction "K_1") (pintype "passive"))
      (node (ref "MMC5603") (pin "A1") (pinfunction "VSA_A1") (pintype "passive"))
      (node (ref "Q3") (pin "2") (pinfunction "S_2") (pintype "passive"))
      (node (ref "Q4") (pin "2") (pinfunction "S_2") (pintype "passive"))
      (node (ref "R13") (pin "1") (pinfunction "1_1") (pintype "passive"))
      (node (ref "R15") (pin "1") (pinfunction "1_1") (pintype "passive"))
      (node (ref "R2") (pin "1") (pinfunction "1_1") (pintype "passive"))
      (node (ref "R22") (pin "2") (pinfunction "2_2") (pintype "passive"))
      (node (ref "SW1") (pin "3") (pinfunction "3_3") (pintype "passive"))
      (node (ref "SW1") (pin "4") (pinfunction "4_4") (pintype "passive"))
      (node (ref "SW1") (pin "5") (pinfunction "5_5") (pintype "passive"))
      (node (ref "TPS61090") (pin "10") (pinfunction "SYNC_10") (pintype "passive"))
      (node (ref "TPS61090") (pin "13") (pinfunction "GND_13") (pintype "passive"))
      (node (ref "TPS61090") (pin "17") (pinfunction "EPAD_17") (pintype "passive"))
      (node (ref "TPS61090") (pin "5") (pinfunction "PGND_5") (pintype "passive"))
      (node (ref "TPS61090") (pin "6") (pinfunction "PGND_6") (pintype "passive"))
      (node (ref "TPS61090") (pin "7") (pinfunction "PGND_7") (pintype "passive"))
      (node (ref "U10") (pin "2") (pinfunction "2_2") (pintype "passive"))
      (node (ref "U10") (pin "4") (pinfunction "4_4") (pintype "passive"))
      (node (ref "U10") (pin "5") (pinfunction "5_5") (pintype "passive"))
      (node (ref "U11") (pin "2") (pinfunction "2_2") (pintype "passive"))
      (node (ref "U11") (pin "4") (pinfunction "4_4") (pintype "passive"))
      (node (ref "U11") (pin "5") (pinfunction "5_5") (pintype "passive"))
      (node (ref "U12") (pin "2") (pinfunction "2_2") (pintype "passive"))
      (node (ref "U12") (pin "4") (pinfunction "4_4") (pintype "passive"))
      (node (ref "U12") (pin "5") (pinfunction "5_5") (pintype "passive"))
      (node (ref "U13") (pin "2") (pinfunction "2_2") (pintype "passive"))
      (node (ref "U13") (pin "4") (pinfunction "4_4") (pintype "passive"))
      (node (ref "U13") (pin "5") (pinfunction "5_5") (pintype "passive"))
      (node (ref "U14") (pin "2") (pinfunction "2_2") (pintype "passive"))
      (node (ref "U14") (pin "4") (pinfunction "4_4") (pintype "passive"))
      (node (ref "U14") (pin "5") (pinfunction "5_5") (pintype "passive"))
      (node (ref "U2") (pin "1") (pinfunction "1_1") (pintype "passive"))
      (node (ref "U3") (pin "6") (pinfunction "GND_6") (pintype "passive"))
      (node (ref "U3") (pin "7") (pinfunction "GND_7") (pintype "passive"))
      (node (ref "U4") (pin "1") (pinfunction "GND_1") (pintype "passive"))
      (node (ref "U5") (pin "8") (pinfunction "GND_8") (pintype "passive"))
      (node (ref "U6") (pin "1") (pinfunction "1_1") (pintype "passive"))
      (node (ref "U6") (pin "3") (pinfunction "3_3") (pintype "passive"))
      (node (ref "U6") (pin "4") (pinfunction "4_4") (pintype "passive"))
      (node (ref "U7") (pin "2") (pinfunction "2_2") (pintype "passive"))
      (node (ref "U7") (pin "3") (pinfunction "3_3") (pintype "passive"))
      (node (ref "U7") (pin "4") (pinfunction "4_4") (pintype "passive"))
      (node (ref "USB-C") (pin "A1B12") (pinfunction "GND_A1B12") (pintype "passive"))
      (node (ref "USB-C") (pin "B1A12") (pinfunction "GND_B1A12") (pintype "passive"))
      (node (ref "USB-C") (pin "EP") (pinfunction "EP_EP") (pintype "passive"))
    )
    (net (code "38") (name "Net-(AT24C256C-A2)") (class "Default")
      (node (ref "AT24C256C") (pin "3") (pinfunction "A2_3") (pintype "passive"))
      (node (ref "ESPR20") (pin "1") (pinfunction "1_1") (pintype "passive"))
    )
    (net (code "39") (name "Net-(CP2102-RST#)") (class "Default")
      (node (ref "CP2102") (pin "9") (pinfunction "RST#_9") (pintype "passive"))
      (node (ref "ESPR12") (pin "2") (pinfunction "2_2") (pintype "passive"))
    )
    (net (code "40") (name "Net-(CP2102-RXD)") (class "Default")
      (node (ref "CP2102") (pin "25") (pinfunction "RXD_25") (pintype "passive"))
      (node (ref "ESPR7") (pin "1") (pinfunction "1_1") (pintype "passive"))
    )
    (net (code "41") (name "Net-(CP2102-SUSPEND#)") (class "Default")
      (node (ref "CP2102") (pin "11") (pinfunction "SUSPEND#_11") (pintype "passive"))
      (node (ref "R13") (pin "2") (pinfunction "2_2") (pintype "passive"))
    )
    (net (code "42") (name "Net-(CP2102-TXD)") (class "Default")
      (node (ref "CP2102") (pin "26") (pinfunction "TXD_26") (pintype "passive"))
      (node (ref "ESPR6") (pin "1") (pinfunction "1_1") (pintype "passive"))
    )
    (net (code "43") (name "Net-(CP2102-VBUS)") (class "Default")
      (node (ref "CP2102") (pin "8") (pinfunction "VBUS_8") (pintype "passive"))
      (node (ref "ESPR10") (pin "2") (pinfunction "2_2") (pintype "passive"))
      (node (ref "ESPR11") (pin "2") (pinfunction "2_2") (pintype "passive"))
    )
    (net (code "44") (name "Net-(D2-A)") (class "Default")
      (node (ref "C11") (pin "2") (pinfunction "2_2") (pintype "passive"))
      (node (ref "C12") (pin "2") (pinfunction "2_2") (pintype "passive"))
      (node (ref "D2") (pin "1") (pinfunction "A_1") (pintype "passive"))
      (node (ref "R21") (pin "1") (pinfunction "1_1") (pintype "passive"))
      (node (ref "TPS61090") (pin "1") (pinfunction "VOUT_1") (pintype "passive"))
      (node (ref "TPS61090") (pin "15") (pinfunction "VOUT_15") (pintype "passive"))
      (node (ref "TPS61090") (pin "16") (pinfunction "VOUT_16") (pintype "passive"))
    )
    (net (code "45") (name "Net-(ESP32-IO0)") (class "Default")
      (node (ref "ESP32") (pin "25") (pinfunction "IO0_25") (pintype "passive"))
      (node (ref "ESPR5") (pin "1") (pinfunction "1_1") (pintype "passive"))
    )
    (net (code "46") (name "Net-(ESPLED2-A)") (class "Default")
      (node (ref "ESPLED2") (pin "1") (pinfunction "A_1") (pintype "passive"))
      (node (ref "ESPR3") (pin "1") (pinfunction "1_1") (pintype "passive"))
    )
    (net (code "47") (name "Net-(ESPQ1-B)") (class "Default")
      (node (ref "ESPQ1") (pin "1") (pinfunction "B_1") (pintype "passive"))
      (node (ref "ESPR17") (pin "1") (pinfunction "1_1") (pintype "passive"))
    )
    (net (code "48") (name "Net-(ESPQ2-B)") (class "Default")
      (node (ref "ESPQ2") (pin "1") (pinfunction "B_1") (pintype "passive"))
      (node (ref "ESPR16") (pin "1") (pinfunction "1_1") (pintype "passive"))
    )
    (net (code "49") (name "Net-(L1-Pad2)") (class "Default")
      (node (ref "L1") (pin "2") (pinfunction "2_2") (pintype "passive"))
      (node (ref "TPS61090") (pin "3") (pinfunction "SW_3") (pintype "passive"))
      (node (ref "TPS61090") (pin "4") (pinfunction "SW_4") (pintype "passive"))
    )
    (net (code "50") (name "Net-(LED1-A)") (class "Default")
      (node (ref "LED1") (pin "2") (pinfunction "A_2") (pintype "passive"))
      (node (ref "R8") (pin "1") (pinfunction "1_1") (pintype "passive"))
    )
    (net (code "51") (name "Net-(Q1-B)") (class "Default")
      (node (ref "Q1") (pin "1") (pinfunction "B_1") (pintype "passive"))
      (node (ref "TPS61090") (pin "12") (pinfunction "LBO_12") (pintype "passive"))
    )
    (net (code "52") (name "Net-(Q1-C)") (class "Default")
      (node (ref "Q1") (pin "3") (pinfunction "C_3") (pintype "passive"))
      (node (ref "R8") (pin "2") (pinfunction "2_2") (pintype "passive"))
    )
    (net (code "53") (name "Net-(Q3-G)") (class "Default")
      (node (ref "C7") (pin "2") (pinfunction "2_2") (pintype "passive"))
      (node (ref "H8") (pin "1") (pinfunction "1_1") (pintype "passive"))
      (node (ref "Q3") (pin "1") (pinfunction "G_1") (pintype "passive"))
      (node (ref "Q4") (pin "1") (pinfunction "G_1") (pintype "passive"))
      (node (ref "R14") (pin "1") (pinfunction "1_1") (pintype "passive"))
      (node (ref "R15") (pin "2") (pinfunction "2_2") (pintype "passive"))
    )
    (net (code "54") (name "Net-(R4-Pad1)") (class "Default")
      (node (ref "R4") (pin "1") (pinfunction "1_1") (pintype "passive"))
      (node (ref "R5") (pin "2") (pinfunction "2_2") (pintype "passive"))
    )
    (net (code "55") (name "Net-(R18-Pad1)") (class "Default")
      (node (ref "R18") (pin "1") (pinfunction "1_1") (pintype "passive"))
      (node (ref "R19") (pin "2") (pinfunction "2_2") (pintype "passive"))
    )
    (net (code "56") (name "Net-(R19-Pad1)") (class "Default")
      (node (ref "R19") (pin "1") (pinfunction "1_1") (pintype "passive"))
      (node (ref "R21") (pin "2") (pinfunction "2_2") (pintype "passive"))
    )
    (net (code "57") (name "Net-(TPS61090-EN)") (class "Default")
      (node (ref "SW1") (pin "2") (pinfunction "2_2") (pintype "passive"))
      (node (ref "TPS61090") (pin "11") (pinfunction "EN_11") (pintype "passive"))
    )
    (net (code "58") (name "Net-(TPS61090-FB)") (class "Default")
      (node (ref "R18") (pin "2") (pinfunction "2_2") (pintype "passive"))
      (node (ref "R22") (pin "1") (pinfunction "1_1") (pintype "passive"))
      (node (ref "TPS61090") (pin "14") (pinfunction "FB_14") (pintype "passive"))
    )
    (net (code "59") (name "Net-(TPS61090-LBI)") (class "Default")
      (node (ref "R2") (pin "2") (pinfunction "2_2") (pintype "passive"))
      (node (ref "R5") (pin "1") (pinfunction "1_1") (pintype "passive"))
      (node (ref "TPS61090") (pin "9") (pinfunction "LBI_9") (pintype "passive"))
    )
    (net (code "60") (name "Net-(U3-SDO{slash}SA0)") (class "Default")
      (node (ref "ESPR19") (pin "2") (pinfunction "2_2") (pintype "passive"))
      (node (ref "U3") (pin "1") (pinfunction "SDO/SA0_1") (pintype "passive"))
    )
    (net (code "61") (name "Net-(U5-OUT-)") (class "Default")
      (node (ref "CN1") (pin "1") (pinfunction "1_1") (pintype "passive"))
      (node (ref "U5") (pin "9") (pinfunction "OUT-_9") (pintype "passive"))
    )
    (net (code "62") (name "Net-(U5-REG)") (class "Default")
      (node (ref "C1") (pin "2") (pinfunction "2_2") (pintype "passive"))
      (node (ref "U5") (pin "1") (pinfunction "REG_1") (pintype "passive"))
    )
    (net (code "63") (name "Net-(USB-C-CC1)") (class "Default")
      (node (ref "ESPR2") (pin "1") (pinfunction "1_1") (pintype "passive"))
      (node (ref "USB-C") (pin "A5") (pinfunction "CC1_A5") (pintype "passive"))
    )
    (net (code "64") (name "Net-(USB-C-CC2)") (class "Default")
      (node (ref "ESPR1") (pin "2") (pinfunction "2_2") (pintype "passive"))
      (node (ref "USB-C") (pin "B5") (pinfunction "CC2_B5") (pintype "passive"))
    )
    (net (code "65") (name "unconnected-(CP2102-CTS-Pad23)") (class "Default")
      (node (ref "CP2102") (pin "23") (pinfunction "CTS_23") (pintype "passive+no_connect"))
    )
    (net (code "66") (name "unconnected-(CP2102-DCD-Pad1)") (class "Default")
      (node (ref "CP2102") (pin "1") (pinfunction "DCD_1") (pintype "passive+no_connect"))
    )
    (net (code "67") (name "unconnected-(CP2102-DSR-Pad27)") (class "Default")
      (node (ref "CP2102") (pin "27") (pinfunction "DSR_27") (pintype "passive+no_connect"))
    )
    (net (code "68") (name "unconnected-(CP2102-NC-Pad10)") (class "Default")
      (node (ref "CP2102") (pin "10") (pinfunction "NC_10") (pintype "passive+no_connect"))
    )
    (net (code "69") (name "unconnected-(CP2102-NC-Pad13)") (class "Default")
      (node (ref "CP2102") (pin "13") (pinfunction "NC_13") (pintype "passive+no_connect"))
    )
    (net (code "70") (name "unconnected-(CP2102-NC-Pad14)") (class "Default")
      (node (ref "CP2102") (pin "14") (pinfunction "NC_14") (pintype "passive+no_connect"))
    )
    (net (code "71") (name "unconnected-(CP2102-NC-Pad15)") (class "Default")
      (node (ref "CP2102") (pin "15") (pinfunction "NC_15") (pintype "passive+no_connect"))
    )
    (net (code "72") (name "unconnected-(CP2102-NC-Pad16)") (class "Default")
      (node (ref "CP2102") (pin "16") (pinfunction "NC_16") (pintype "passive+no_connect"))
    )
    (net (code "73") (name "unconnected-(CP2102-NC-Pad17)") (class "Default")
      (node (ref "CP2102") (pin "17") (pinfunction "NC_17") (pintype "passive+no_connect"))
    )
    (net (code "74") (name "unconnected-(CP2102-NC-Pad18)") (class "Default")
      (node (ref "CP2102") (pin "18") (pinfunction "NC_18") (pintype "passive+no_connect"))
    )
    (net (code "75") (name "unconnected-(CP2102-NC-Pad19)") (class "Default")
      (node (ref "CP2102") (pin "19") (pinfunction "NC_19") (pintype "passive+no_connect"))
    )
    (net (code "76") (name "unconnected-(CP2102-NC-Pad20)") (class "Default")
      (node (ref "CP2102") (pin "20") (pinfunction "NC_20") (pintype "passive+no_connect"))
    )
    (net (code "77") (name "unconnected-(CP2102-NC-Pad21)") (class "Default")
      (node (ref "CP2102") (pin "21") (pinfunction "NC_21") (pintype "passive+no_connect"))
    )
    (net (code "78") (name "unconnected-(CP2102-NC-Pad22)") (class "Default")
      (node (ref "CP2102") (pin "22") (pinfunction "NC_22") (pintype "passive+no_connect"))
    )
    (net (code "79") (name "unconnected-(CP2102-RI-Pad2)") (class "Default")
      (node (ref "CP2102") (pin "2") (pinfunction "RI_2") (pintype "passive+no_connect"))
    )
    (net (code "80") (name "unconnected-(CP2102-SUSPEND-Pad12)") (class "Default")
      (node (ref "CP2102") (pin "12") (pinfunction "SUSPEND_12") (pintype "passive+no_connect"))
    )
    (net (code "81") (name "unconnected-(ESP32-NC-Pad17)") (class "Default")
      (node (ref "ESP32") (pin "17") (pinfunction "NC_17") (pintype "passive+no_connect"))
    )
    (net (code "82") (name "unconnected-(ESP32-NC-Pad18)") (class "Default")
      (node (ref "ESP32") (pin "18") (pinfunction "NC_18") (pintype "passive+no_connect"))
    )
    (net (code "83") (name "unconnected-(ESP32-NC-Pad19)") (class "Default")
      (node (ref "ESP32") (pin "19") (pinfunction "NC_19") (pintype "passive+no_connect"))
    )
    (net (code "84") (name "unconnected-(ESP32-NC-Pad20)") (class "Default")
      (node (ref "ESP32") (pin "20") (pinfunction "NC_20") (pintype "passive+no_connect"))
    )
    (net (code "85") (name "unconnected-(ESP32-NC-Pad21)") (class "Default")
      (node (ref "ESP32") (pin "21") (pinfunction "NC_21") (pintype "passive+no_connect"))
    )
    (net (code "86") (name "unconnected-(ESP32-NC-Pad22)") (class "Default")
      (node (ref "ESP32") (pin "22") (pinfunction "NC_22") (pintype "passive+no_connect"))
    )
    (net (code "87") (name "unconnected-(ESP32-NC-Pad32)") (class "Default")
      (node (ref "ESP32") (pin "32") (pinfunction "NC_32") (pintype "passive+no_connect"))
    )
    (net (code "88") (name "unconnected-(TPS61090-NC-Pad2)") (class "Default")
      (node (ref "TPS61090") (pin "2") (pinfunction "NC_2") (pintype "passive+no_connect"))
    )
    (net (code "89") (name "unconnected-(U3-CS-Pad12)") (class "Default")
      (node (ref "U3") (pin "12") (pinfunction "CS_12") (pintype "passive+no_connect"))
    )
    (net (code "90") (name "unconnected-(U3-INT1-Pad4)") (class "Default")
      (node (ref "U3") (pin "4") (pinfunction "INT1_4") (pintype "passive+no_connect"))
    )
    (net (code "91") (name "unconnected-(U3-INT2-Pad9)") (class "Default")
      (node (ref "U3") (pin "9") (pinfunction "INT2_9") (pintype "passive+no_connect"))
    )
    (net (code "92") (name "unconnected-(U3-NC-Pad10)") (class "Default")
      (node (ref "U3") (pin "10") (pinfunction "NC_10") (pintype "passive+no_connect"))
    )
    (net (code "93") (name "unconnected-(U3-NC-Pad11)") (class "Default")
      (node (ref "U3") (pin "11") (pinfunction "NC_11") (pintype "passive+no_connect"))
    )
    (net (code "94") (name "unconnected-(U3-SCx-Pad3)") (class "Default")
      (node (ref "U3") (pin "3") (pinfunction "SCx_3") (pintype "passive+no_connect"))
    )
    (net (code "95") (name "unconnected-(U3-SDx-Pad2)") (class "Default")
      (node (ref "U3") (pin "2") (pinfunction "SDx_2") (pintype "passive+no_connect"))
    )
    (net (code "96") (name "unconnected-(U5-IN{slash}TRIG-Pad4)") (class "Default")
      (node (ref "U5") (pin "4") (pinfunction "IN/TRIG_4") (pintype "passive+no_connect"))
    )
    (net (code "97") (name "unconnected-(USB-C-SBU1-PadA8)") (class "Default")
      (node (ref "USB-C") (pin "A8") (pinfunction "SBU1_A8") (pintype "passive+no_connect"))
    )
    (net (code "98") (name "unconnected-(USB-C-SBU2-PadB8)") (class "Default")
      (node (ref "USB-C") (pin "B8") (pinfunction "SBU2_B8") (pintype "passive+no_connect"))
    )
  )
)
